# SFP_Connector.net
KiCad netlist of a schematic drawn in Altium Designer
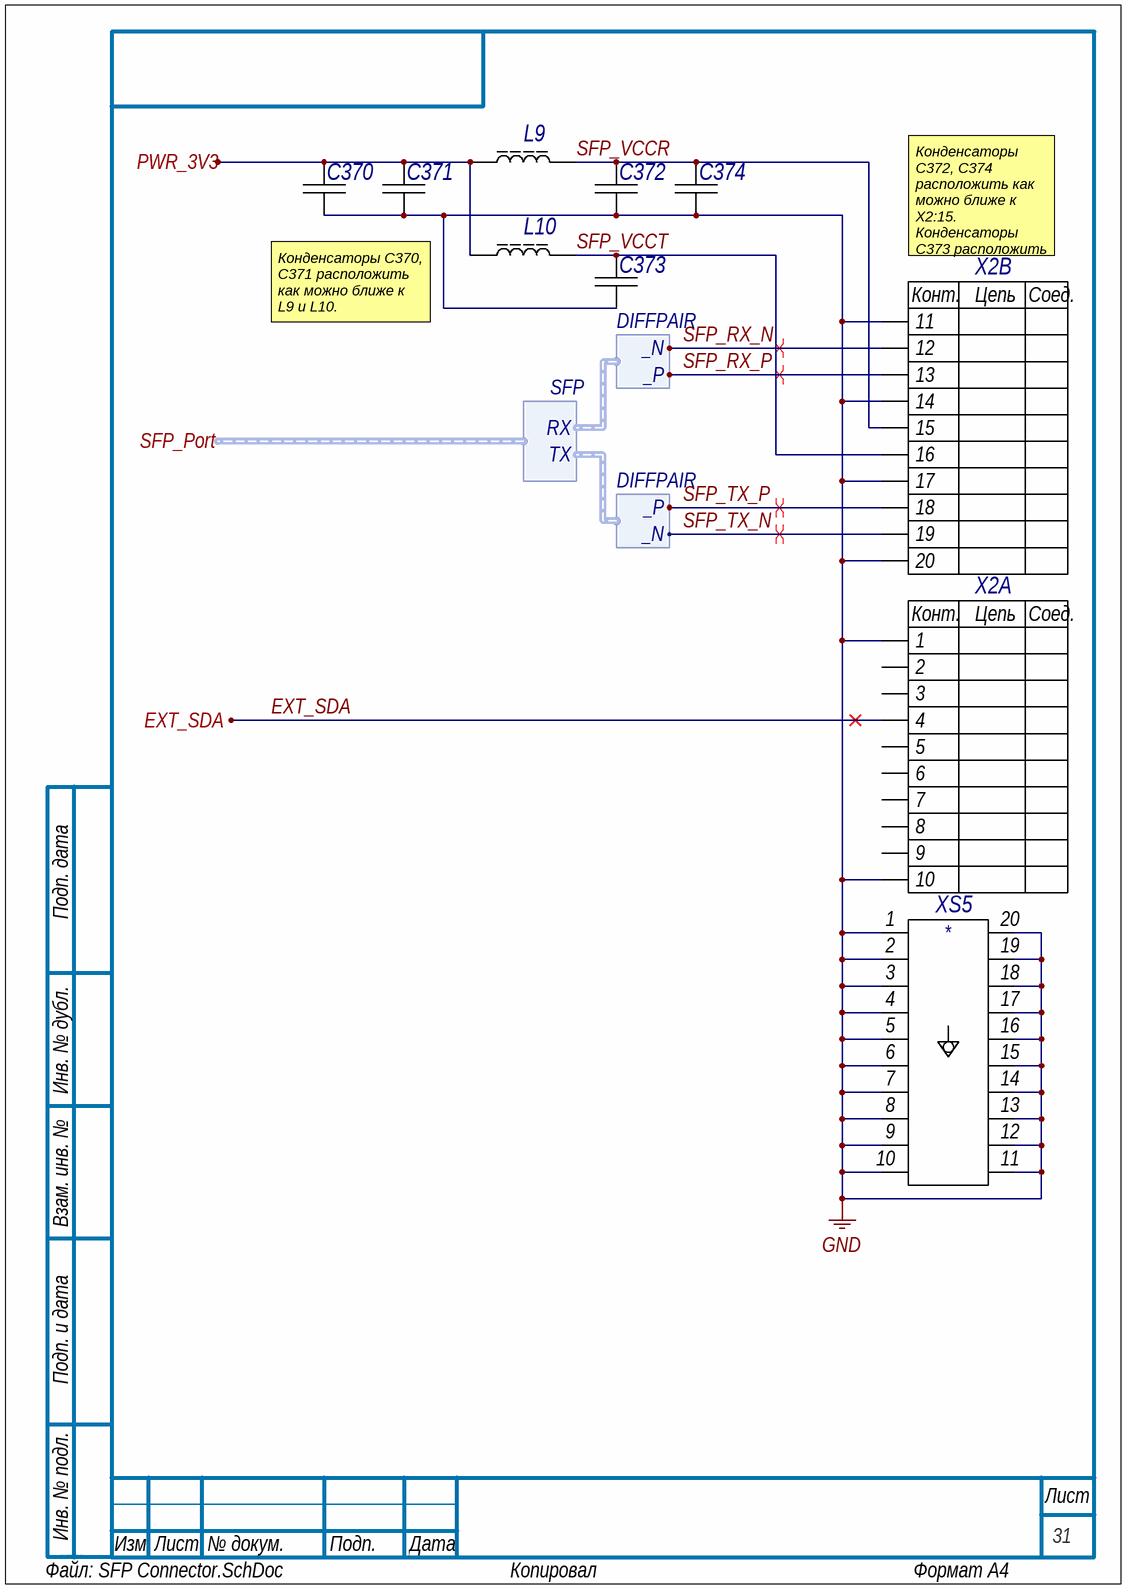
[diagram p0: SFP Connector.SchDoc]

(export (version "E")
  (design (tool "Eeschema 10.0.6"))
  (components
    (comp (ref "C370")
      (value "C1005X7R1E104M")
      (footprint "CAPC1005X55X10LL05")
      (description "Chip Capacitor, 0.1 uF, +/- 20%, 25 V, -55 to 125 degC, 0402 (1005 Metric), RoHS, Tape and Reel")
      (fields (field (name "TOLERANCE") "20%"))
      (libsource (lib "MiniPC DB") (part "CAP_NP"))
    )
    (comp (ref "C371")
      (value "C2012X5R1C106K085AC")
      (footprint "CAPC2013X100X20NL20")
      (description "Chip Capacitor, 10 uF, +/- 10%, 16 V, -55 to 85 degC, 0805 (2012 Metric), RoHS, Tape and Reel")
      (fields (field (name "TOLERANCE") "10%"))
      (libsource (lib "MiniPC DB") (part "CAP_NP"))
    )
    (comp (ref "C372")
      (value "C1005X7R1E104M")
      (footprint "CAPC1005X55X10LL05")
      (description "Chip Capacitor, 0.1 uF, +/- 20%, 25 V, -55 to 125 degC, 0402 (1005 Metric), RoHS, Tape and Reel")
      (fields (field (name "TOLERANCE") "20%"))
      (libsource (lib "MiniPC DB") (part "CAP_NP"))
    )
    (comp (ref "C373")
      (value "C1005X7R1E104M")
      (footprint "CAPC1005X55X10LL05")
      (description "Chip Capacitor, 0.1 uF, +/- 20%, 25 V, -55 to 125 degC, 0402 (1005 Metric), RoHS, Tape and Reel")
      (fields (field (name "TOLERANCE") "20%"))
      (libsource (lib "MiniPC DB") (part "CAP_NP"))
    )
    (comp (ref "C374")
      (value "C2012X5R1C106K085AC")
      (footprint "CAPC2013X100X20NL20")
      (description "Chip Capacitor, 10 uF, +/- 10%, 16 V, -55 to 85 degC, 0805 (2012 Metric), RoHS, Tape and Reel")
      (fields (field (name "TOLERANCE") "10%"))
      (libsource (lib "MiniPC DB") (part "CAP_NP"))
    )
    (comp (ref "L9")
      (value "1008CS-102XFLC")
      (footprint "COIL-1008CS_V")
      (description "Chip Inductor, 1000 nH, +/- 1%, -40 to 125 degC, 2-Pin SMD, RoHS, Tape and Reel")
      (libsource (lib "MiniPC DB") (part "Choke"))
    )
    (comp (ref "L10")
      (value "1008CS-102XFLC")
      (footprint "COIL-1008CS_V")
      (description "Chip Inductor, 1000 nH, +/- 1%, -40 to 125 degC, 2-Pin SMD, RoHS, Tape and Reel")
      (libsource (lib "MiniPC DB") (part "Choke"))
    )
    (comp (ref "X2")
      (value "MECT-110-01-M-D-RA1")
      (footprint "SMTC-MECT-110-01-M-D-RA1_V")
      (fields (field (name "MANUFACTURER") "Samtec"))
      (libsource (lib "MiniPC DB") (part "SOED_20K"))
    )
    (comp (ref "XS5")
      (value "74754-0101")
      (footprint "MOLX-74754-0101_V")
      (description "SFP+ Cage, Single Port, Height 10.85 mm, Tail Height 3.05 mm, -40 to 85 degC, RoHS, Tray")
      (fields (field (name "MANUFACTURER") "Molex"))
      (libsource (lib "MiniPC DB") (part "0747540101"))
    )
  )
  (nets
    (net (code "4") (name "/EXT_SDA") (class "Default")
      (node (ref "X2") (pin "4") (pinfunction "4_4") (pintype "passive"))
    )
    (net (code "5") (name "/PWR_3V3") (class "Default")
      (node (ref "C370") (pin "2") (pinfunction "2_2") (pintype "passive"))
      (node (ref "C371") (pin "2") (pinfunction "2_2") (pintype "passive"))
      (node (ref "L10") (pin "1") (pinfunction "1_1") (pintype "passive"))
      (node (ref "L9") (pin "1") (pinfunction "1_1") (pintype "passive"))
    )
    (net (code "7") (name "/SFP_RX_N") (class "Default")
      (node (ref "X2") (pin "12") (pinfunction "12_12") (pintype "passive"))
    )
    (net (code "8") (name "/SFP_RX_P") (class "Default")
      (node (ref "X2") (pin "13") (pinfunction "13_13") (pintype "passive"))
    )
    (net (code "9") (name "/SFP_TX_N") (class "Default")
      (node (ref "X2") (pin "19") (pinfunction "19_19") (pintype "passive"))
    )
    (net (code "10") (name "/SFP_TX_P") (class "Default")
      (node (ref "X2") (pin "18") (pinfunction "18_18") (pintype "passive"))
    )
    (net (code "11") (name "/SFP_VCCR") (class "Default")
      (node (ref "C372") (pin "2") (pinfunction "2_2") (pintype "passive"))
      (node (ref "C374") (pin "2") (pinfunction "2_2") (pintype "passive"))
      (node (ref "L9") (pin "2") (pinfunction "2_2") (pintype "passive"))
      (node (ref "X2") (pin "15") (pinfunction "15_15") (pintype "passive"))
    )
    (net (code "12") (name "/SFP_VCCT") (class "Default")
      (node (ref "C373") (pin "2") (pinfunction "2_2") (pintype "passive"))
      (node (ref "L10") (pin "2") (pinfunction "2_2") (pintype "passive"))
      (node (ref "X2") (pin "16") (pinfunction "16_16") (pintype "passive"))
    )
    (net (code "15") (name "GND") (class "Default")
      (node (ref "C370") (pin "1") (pinfunction "1_1") (pintype "passive"))
      (node (ref "C371") (pin "1") (pinfunction "1_1") (pintype "passive"))
      (node (ref "C372") (pin "1") (pinfunction "1_1") (pintype "passive"))
      (node (ref "C373") (pin "1") (pinfunction "1_1") (pintype "passive"))
      (node (ref "C374") (pin "1") (pinfunction "1_1") (pintype "passive"))
      (node (ref "X2") (pin "1") (pinfunction "1_1") (pintype "passive"))
      (node (ref "X2") (pin "10") (pinfunction "10_10") (pintype "passive"))
      (node (ref "X2") (pin "11") (pinfunction "11_11") (pintype "passive"))
      (node (ref "X2") (pin "14") (pinfunction "14_14") (pintype "passive"))
      (node (ref "X2") (pin "17") (pinfunction "17_17") (pintype "passive"))
      (node (ref "X2") (pin "20") (pinfunction "20_20") (pintype "passive"))
      (node (ref "XS5") (pin "1") (pinfunction "1_1") (pintype "passive"))
      (node (ref "XS5") (pin "10") (pinfunction "10_10") (pintype "passive"))
      (node (ref "XS5") (pin "11") (pinfunction "11_11") (pintype "passive"))
      (node (ref "XS5") (pin "12") (pinfunction "12_12") (pintype "passive"))
      (node (ref "XS5") (pin "13") (pinfunction "13_13") (pintype "passive"))
      (node (ref "XS5") (pin "14") (pinfunction "14_14") (pintype "passive"))
      (node (ref "XS5") (pin "15") (pinfunction "15_15") (pintype "passive"))
      (node (ref "XS5") (pin "16") (pinfunction "16_16") (pintype "passive"))
      (node (ref "XS5") (pin "17") (pinfunction "17_17") (pintype "passive"))
      (node (ref "XS5") (pin "18") (pinfunction "18_18") (pintype "passive"))
      (node (ref "XS5") (pin "19") (pinfunction "19_19") (pintype "passive"))
      (node (ref "XS5") (pin "2") (pinfunction "2_2") (pintype "passive"))
      (node (ref "XS5") (pin "20") (pinfunction "20_20") (pintype "passive"))
      (node (ref "XS5") (pin "3") (pinfunction "3_3") (pintype "passive"))
      (node (ref "XS5") (pin "4") (pinfunction "4_4") (pintype "passive"))
      (node (ref "XS5") (pin "5") (pinfunction "5_5") (pintype "passive"))
      (node (ref "XS5") (pin "6") (pinfunction "6_6") (pintype "passive"))
      (node (ref "XS5") (pin "7") (pinfunction "7_7") (pintype "passive"))
      (node (ref "XS5") (pin "8") (pinfunction "8_8") (pintype "passive"))
      (node (ref "XS5") (pin "9") (pinfunction "9_9") (pintype "passive"))
    )
    (net (code "16") (name "unconnected-(X2-Pad2)") (class "Default")
      (node (ref "X2") (pin "2") (pinfunction "2_2") (pintype "passive"))
    )
    (net (code "17") (name "unconnected-(X2-Pad3)") (class "Default")
      (node (ref "X2") (pin "3") (pinfunction "3_3") (pintype "passive"))
    )
    (net (code "18") (name "unconnected-(X2-Pad5)") (class "Default")
      (node (ref "X2") (pin "5") (pinfunction "5_5") (pintype "passive"))
    )
    (net (code "19") (name "unconnected-(X2-Pad6)") (class "Default")
      (node (ref "X2") (pin "6") (pinfunction "6_6") (pintype "passive"))
    )
    (net (code "20") (name "unconnected-(X2-Pad7)") (class "Default")
      (node (ref "X2") (pin "7") (pinfunction "7_7") (pintype "passive"))
    )
    (net (code "21") (name "unconnected-(X2-Pad8)") (class "Default")
      (node (ref "X2") (pin "8") (pinfunction "8_8") (pintype "passive"))
    )
    (net (code "22") (name "unconnected-(X2-Pad9)") (class "Default")
      (node (ref "X2") (pin "9") (pinfunction "9_9") (pintype "passive"))
    )
  )
)
